# LC_LPF13.net
KiCad netlist of a schematic drawn in Altium Designer
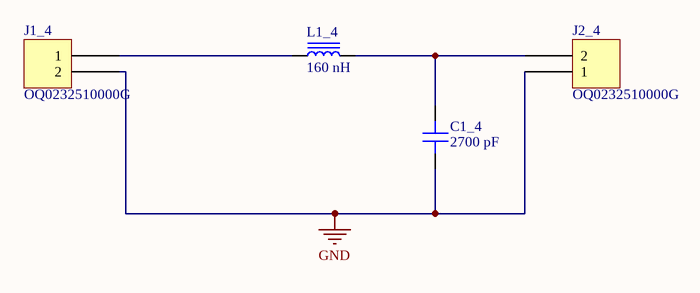
[diagram p0: LC_LPF13.SchDoc]

(export (version "E")
  (design (tool "Eeschema 10.0.6"))
  (components
    (comp (ref "C1_4")
      (value "2700 pF")
      (footprint "CAP 0603_1608")
      (description "CAP CER 2700PF 25V NP0 0603")
      (fields (field (name "PART NUMBER") "C0603C272F3GAC7867") (field (name "MANUFACTURER") "KEMET"))
      (libsource (lib "Celestial Altium Library - altium_library") (part "Capacitor"))
    )
    (comp (ref "J1_4")
      (value "OQ0232510000G")
      (footprint "FCI 06-381-2PIN")
      (description "TERM BLOCK HDR 2POS 90DEG 3.81MM")
      (fields (field (name "MANUFACTURER") "Amphenol Anytek"))
      (libsource (lib "Celestial Altium Library - altium_library") (part "2 Pin"))
    )
    (comp (ref "J2_4")
      (value "OQ0232510000G")
      (footprint "FCI 06-381-2PIN")
      (description "TERM BLOCK HDR 2POS 90DEG 3.81MM")
      (fields (field (name "MANUFACTURER") "Amphenol Anytek"))
      (libsource (lib "") (part "2 Pin_1"))
    )
    (comp (ref "L1_4")
      (value "160 nH")
      (footprint "IND 0402_1005 RF WW")
      (description "FIXED IND 160NH 480MA 330MOHM SM")
      (fields
        (field (name "PART NUMBER") "LQW15CNR16J00D")
        (field (name "MANUFACTURER") "Murata Electronics")
      )
      (libsource (lib "Celestial Altium Library - altium_library") (part "Inductor"))
    )
  )
  (nets
    (net (code "1") (name "GND") (class "Default")
      (node (ref "C1_4") (pin "1") (pinfunction "1_1") (pintype "passive"))
      (node (ref "J1_4") (pin "2") (pinfunction "2_2") (pintype "passive"))
      (node (ref "J2_4") (pin "1") (pinfunction "1_1") (pintype "passive"))
    )
    (net (code "2") (name "Net-(C1_4-Pad2)") (class "Default")
      (node (ref "C1_4") (pin "2") (pinfunction "2_2") (pintype "passive"))
      (node (ref "J2_4") (pin "2") (pinfunction "2_2") (pintype "passive"))
      (node (ref "L1_4") (pin "2") (pinfunction "2_2") (pintype "passive"))
    )
    (net (code "3") (name "Net-(J1_4-Pad1)") (class "Default")
      (node (ref "J1_4") (pin "1") (pinfunction "1_1") (pintype "passive"))
      (node (ref "L1_4") (pin "1") (pinfunction "1_1") (pintype "passive"))
    )
  )
)
